# sensor_board.net
KiCad netlist of a schematic drawn in EasyEDA Pro
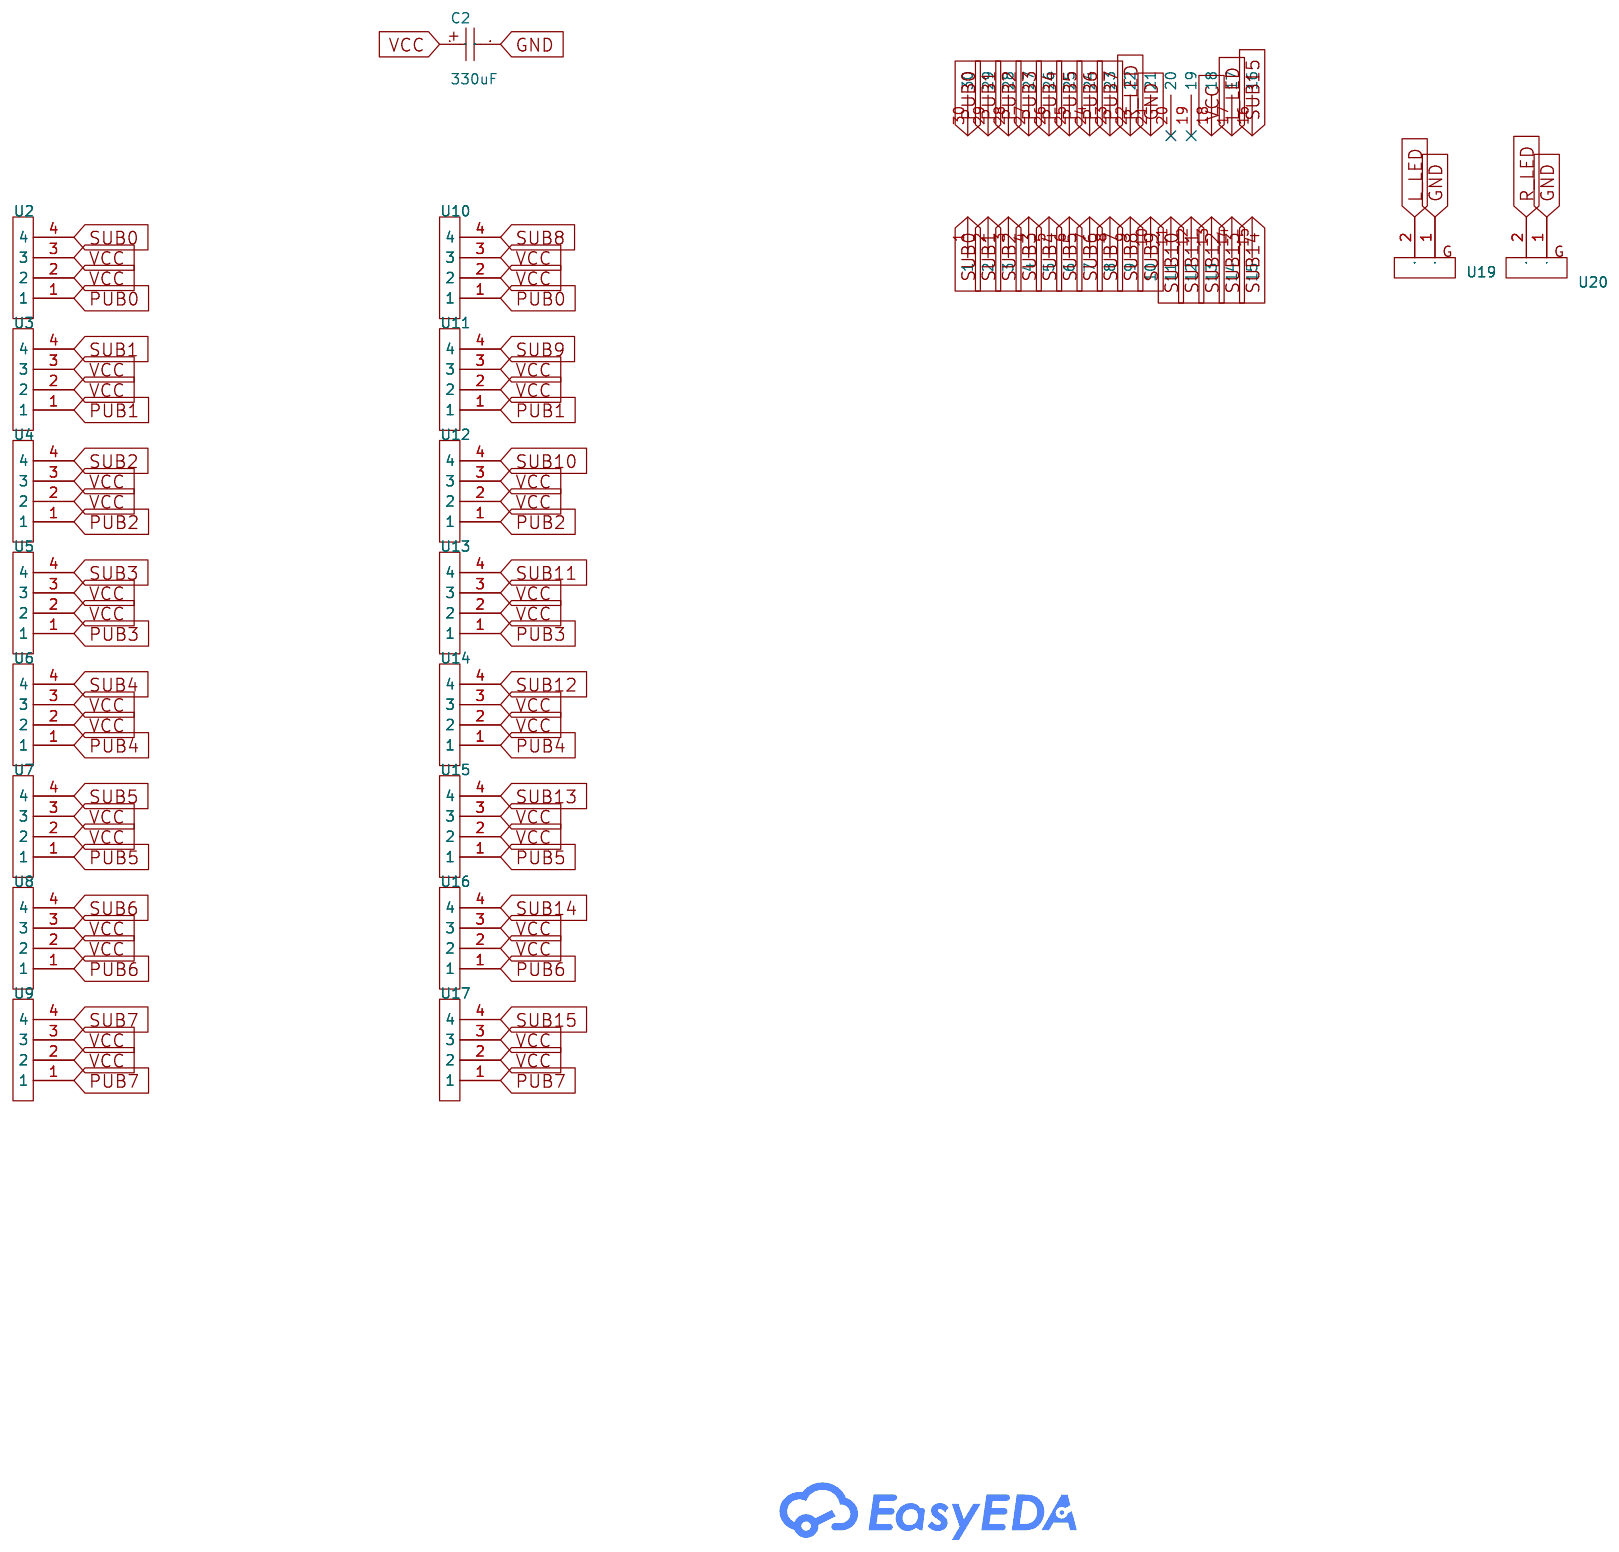
[diagram p0: schematic sheet]

(export (version "E")
  (design (tool "Eeschema 10.0.6"))
  (components
    (comp (ref "C2")
      (value "330uF")
      (footprint "easyedapro:CASE-D_7343")
      (fields (field (name "Manufacturer Part") "TAJD337M006RNJ") (field (name "Manufacturer") "Kyocera AVX"))
      (libsource (lib "easyedapro") (part "TAJD337M006RNJ"))
    )
    (comp (ref "U1")
      (value "~")
      (footprint "easyedapro:header_pin(2*15)")
      (libsource (lib "easyedapro") (part "header_pin(2_15)"))
    )
    (comp (ref "U2") (value "~") (footprint "easyedapro:4pin") (libsource (lib "easyedapro") (part "4pin")))
    (comp (ref "U3") (value "~") (footprint "easyedapro:4pin") (libsource (lib "easyedapro") (part "4pin")))
    (comp (ref "U4") (value "~") (footprint "easyedapro:4pin") (libsource (lib "easyedapro") (part "4pin")))
    (comp (ref "U5") (value "~") (footprint "easyedapro:4pin") (libsource (lib "easyedapro") (part "4pin")))
    (comp (ref "U6") (value "~") (footprint "easyedapro:4pin") (libsource (lib "easyedapro") (part "4pin")))
    (comp (ref "U7") (value "~") (footprint "easyedapro:4pin") (libsource (lib "easyedapro") (part "4pin")))
    (comp (ref "U8") (value "~") (footprint "easyedapro:4pin") (libsource (lib "easyedapro") (part "4pin")))
    (comp (ref "U9") (value "~") (footprint "easyedapro:4pin") (libsource (lib "easyedapro") (part "4pin")))
    (comp (ref "U10") (value "~") (footprint "easyedapro:4pin") (libsource (lib "easyedapro") (part "4pin")))
    (comp (ref "U11") (value "~") (footprint "easyedapro:4pin") (libsource (lib "easyedapro") (part "4pin")))
    (comp (ref "U12") (value "~") (footprint "easyedapro:4pin") (libsource (lib "easyedapro") (part "4pin")))
    (comp (ref "U13") (value "~") (footprint "easyedapro:4pin") (libsource (lib "easyedapro") (part "4pin")))
    (comp (ref "U14") (value "~") (footprint "easyedapro:4pin") (libsource (lib "easyedapro") (part "4pin")))
    (comp (ref "U15") (value "~") (footprint "easyedapro:4pin") (libsource (lib "easyedapro") (part "4pin")))
    (comp (ref "U16") (value "~") (footprint "easyedapro:4pin") (libsource (lib "easyedapro") (part "4pin")))
    (comp (ref "U17") (value "~") (footprint "easyedapro:4pin") (libsource (lib "easyedapro") (part "4pin")))
    (comp (ref "U19")
      (value "~")
      (footprint "easyedapro:pub_pin")
      (libsource (lib "easyedapro") (part "pub_pin"))
    )
    (comp (ref "U20")
      (value "~")
      (footprint "easyedapro:pub_pin")
      (libsource (lib "easyedapro") (part "pub_pin"))
    )
  )
  (nets
    (net (code "1") (name "GND") (class "Default")
      (node (ref "C2") (pin "2") (pinfunction "2_2") (pintype "input"))
      (node (ref "U1") (pin "21") (pinfunction "21_21") (pintype "input"))
      (node (ref "U19") (pin "1") (pinfunction "1_1") (pintype "input"))
      (node (ref "U20") (pin "1") (pinfunction "1_1") (pintype "input"))
    )
    (net (code "2") (name "L_LED") (class "Default")
      (node (ref "U1") (pin "17") (pinfunction "17_17") (pintype "input"))
      (node (ref "U19") (pin "2") (pinfunction "2_2") (pintype "input"))
    )
    (net (code "3") (name "PUB0") (class "Default")
      (node (ref "U1") (pin "30") (pinfunction "30_30") (pintype "input"))
      (node (ref "U10") (pin "1") (pinfunction "1_1") (pintype "input"))
      (node (ref "U2") (pin "1") (pinfunction "1_1") (pintype "input"))
    )
    (net (code "4") (name "PUB1") (class "Default")
      (node (ref "U1") (pin "29") (pinfunction "29_29") (pintype "input"))
      (node (ref "U11") (pin "1") (pinfunction "1_1") (pintype "input"))
      (node (ref "U3") (pin "1") (pinfunction "1_1") (pintype "input"))
    )
    (net (code "5") (name "PUB2") (class "Default")
      (node (ref "U1") (pin "28") (pinfunction "28_28") (pintype "input"))
      (node (ref "U12") (pin "1") (pinfunction "1_1") (pintype "input"))
      (node (ref "U4") (pin "1") (pinfunction "1_1") (pintype "input"))
    )
    (net (code "6") (name "PUB3") (class "Default")
      (node (ref "U1") (pin "27") (pinfunction "27_27") (pintype "input"))
      (node (ref "U13") (pin "1") (pinfunction "1_1") (pintype "input"))
      (node (ref "U5") (pin "1") (pinfunction "1_1") (pintype "input"))
    )
    (net (code "7") (name "PUB4") (class "Default")
      (node (ref "U1") (pin "26") (pinfunction "26_26") (pintype "input"))
      (node (ref "U14") (pin "1") (pinfunction "1_1") (pintype "input"))
      (node (ref "U6") (pin "1") (pinfunction "1_1") (pintype "input"))
    )
    (net (code "8") (name "PUB5") (class "Default")
      (node (ref "U1") (pin "25") (pinfunction "25_25") (pintype "input"))
      (node (ref "U15") (pin "1") (pinfunction "1_1") (pintype "input"))
      (node (ref "U7") (pin "1") (pinfunction "1_1") (pintype "input"))
    )
    (net (code "9") (name "PUB6") (class "Default")
      (node (ref "U1") (pin "24") (pinfunction "24_24") (pintype "input"))
      (node (ref "U16") (pin "1") (pinfunction "1_1") (pintype "input"))
      (node (ref "U8") (pin "1") (pinfunction "1_1") (pintype "input"))
    )
    (net (code "10") (name "PUB7") (class "Default")
      (node (ref "U1") (pin "23") (pinfunction "23_23") (pintype "input"))
      (node (ref "U17") (pin "1") (pinfunction "1_1") (pintype "input"))
      (node (ref "U9") (pin "1") (pinfunction "1_1") (pintype "input"))
    )
    (net (code "11") (name "R_LED") (class "Default")
      (node (ref "U1") (pin "22") (pinfunction "22_22") (pintype "input"))
      (node (ref "U20") (pin "2") (pinfunction "2_2") (pintype "input"))
    )
    (net (code "12") (name "SUB0") (class "Default")
      (node (ref "U1") (pin "1") (pinfunction "1_1") (pintype "input"))
      (node (ref "U2") (pin "4") (pinfunction "4_4") (pintype "input"))
    )
    (net (code "13") (name "SUB1") (class "Default")
      (node (ref "U1") (pin "2") (pinfunction "2_2") (pintype "input"))
      (node (ref "U3") (pin "4") (pinfunction "4_4") (pintype "input"))
    )
    (net (code "14") (name "SUB2") (class "Default")
      (node (ref "U1") (pin "3") (pinfunction "3_3") (pintype "input"))
      (node (ref "U4") (pin "4") (pinfunction "4_4") (pintype "input"))
    )
    (net (code "15") (name "SUB3") (class "Default")
      (node (ref "U1") (pin "4") (pinfunction "4_4") (pintype "input"))
      (node (ref "U5") (pin "4") (pinfunction "4_4") (pintype "input"))
    )
    (net (code "16") (name "SUB4") (class "Default")
      (node (ref "U1") (pin "5") (pinfunction "5_5") (pintype "input"))
      (node (ref "U6") (pin "4") (pinfunction "4_4") (pintype "input"))
    )
    (net (code "17") (name "SUB5") (class "Default")
      (node (ref "U1") (pin "6") (pinfunction "6_6") (pintype "input"))
      (node (ref "U7") (pin "4") (pinfunction "4_4") (pintype "input"))
    )
    (net (code "18") (name "SUB6") (class "Default")
      (node (ref "U1") (pin "7") (pinfunction "7_7") (pintype "input"))
      (node (ref "U8") (pin "4") (pinfunction "4_4") (pintype "input"))
    )
    (net (code "19") (name "SUB7") (class "Default")
      (node (ref "U1") (pin "8") (pinfunction "8_8") (pintype "input"))
      (node (ref "U9") (pin "4") (pinfunction "4_4") (pintype "input"))
    )
    (net (code "20") (name "SUB8") (class "Default")
      (node (ref "U1") (pin "9") (pinfunction "9_9") (pintype "input"))
      (node (ref "U10") (pin "4") (pinfunction "4_4") (pintype "input"))
    )
    (net (code "21") (name "SUB9") (class "Default")
      (node (ref "U1") (pin "10") (pinfunction "10_10") (pintype "input"))
      (node (ref "U11") (pin "4") (pinfunction "4_4") (pintype "input"))
    )
    (net (code "22") (name "SUB10") (class "Default")
      (node (ref "U1") (pin "11") (pinfunction "11_11") (pintype "input"))
      (node (ref "U12") (pin "4") (pinfunction "4_4") (pintype "input"))
    )
    (net (code "23") (name "SUB11") (class "Default")
      (node (ref "U1") (pin "12") (pinfunction "12_12") (pintype "input"))
      (node (ref "U13") (pin "4") (pinfunction "4_4") (pintype "input"))
    )
    (net (code "24") (name "SUB12") (class "Default")
      (node (ref "U1") (pin "13") (pinfunction "13_13") (pintype "input"))
      (node (ref "U14") (pin "4") (pinfunction "4_4") (pintype "input"))
    )
    (net (code "25") (name "SUB13") (class "Default")
      (node (ref "U1") (pin "14") (pinfunction "14_14") (pintype "input"))
      (node (ref "U15") (pin "4") (pinfunction "4_4") (pintype "input"))
    )
    (net (code "26") (name "SUB14") (class "Default")
      (node (ref "U1") (pin "15") (pinfunction "15_15") (pintype "input"))
      (node (ref "U16") (pin "4") (pinfunction "4_4") (pintype "input"))
    )
    (net (code "27") (name "SUB15") (class "Default")
      (node (ref "U1") (pin "16") (pinfunction "16_16") (pintype "input"))
      (node (ref "U17") (pin "4") (pinfunction "4_4") (pintype "input"))
    )
    (net (code "28") (name "VCC") (class "Default")
      (node (ref "C2") (pin "1") (pinfunction "1_1") (pintype "input"))
      (node (ref "U1") (pin "18") (pinfunction "18_18") (pintype "input"))
      (node (ref "U10") (pin "2") (pinfunction "2_2") (pintype "input"))
      (node (ref "U10") (pin "3") (pinfunction "3_3") (pintype "input"))
      (node (ref "U11") (pin "2") (pinfunction "2_2") (pintype "input"))
      (node (ref "U11") (pin "3") (pinfunction "3_3") (pintype "input"))
      (node (ref "U12") (pin "2") (pinfunction "2_2") (pintype "input"))
      (node (ref "U12") (pin "3") (pinfunction "3_3") (pintype "input"))
      (node (ref "U13") (pin "2") (pinfunction "2_2") (pintype "input"))
      (node (ref "U13") (pin "3") (pinfunction "3_3") (pintype "input"))
      (node (ref "U14") (pin "2") (pinfunction "2_2") (pintype "input"))
      (node (ref "U14") (pin "3") (pinfunction "3_3") (pintype "input"))
      (node (ref "U15") (pin "2") (pinfunction "2_2") (pintype "input"))
      (node (ref "U15") (pin "3") (pinfunction "3_3") (pintype "input"))
      (node (ref "U16") (pin "2") (pinfunction "2_2") (pintype "input"))
      (node (ref "U16") (pin "3") (pinfunction "3_3") (pintype "input"))
      (node (ref "U17") (pin "2") (pinfunction "2_2") (pintype "input"))
      (node (ref "U17") (pin "3") (pinfunction "3_3") (pintype "input"))
      (node (ref "U2") (pin "2") (pinfunction "2_2") (pintype "input"))
      (node (ref "U2") (pin "3") (pinfunction "3_3") (pintype "input"))
      (node (ref "U3") (pin "2") (pinfunction "2_2") (pintype "input"))
      (node (ref "U3") (pin "3") (pinfunction "3_3") (pintype "input"))
      (node (ref "U4") (pin "2") (pinfunction "2_2") (pintype "input"))
      (node (ref "U4") (pin "3") (pinfunction "3_3") (pintype "input"))
      (node (ref "U5") (pin "2") (pinfunction "2_2") (pintype "input"))
      (node (ref "U5") (pin "3") (pinfunction "3_3") (pintype "input"))
      (node (ref "U6") (pin "2") (pinfunction "2_2") (pintype "input"))
      (node (ref "U6") (pin "3") (pinfunction "3_3") (pintype "input"))
      (node (ref "U7") (pin "2") (pinfunction "2_2") (pintype "input"))
      (node (ref "U7") (pin "3") (pinfunction "3_3") (pintype "input"))
      (node (ref "U8") (pin "2") (pinfunction "2_2") (pintype "input"))
      (node (ref "U8") (pin "3") (pinfunction "3_3") (pintype "input"))
      (node (ref "U9") (pin "2") (pinfunction "2_2") (pintype "input"))
      (node (ref "U9") (pin "3") (pinfunction "3_3") (pintype "input"))
    )
    (net (code "29") (name "unconnected-(U1-Pad19)") (class "Default")
      (node (ref "U1") (pin "19") (pinfunction "19_19") (pintype "input+no_connect"))
    )
    (net (code "30") (name "unconnected-(U1-Pad20)") (class "Default")
      (node (ref "U1") (pin "20") (pinfunction "20_20") (pintype "input+no_connect"))
    )
  )
)
